# CON_VIDEO_IN.net
KiCad netlist of a schematic drawn in Altium Designer
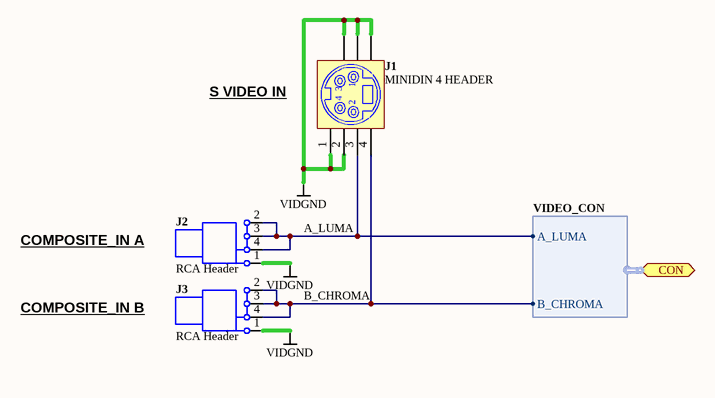
[diagram p0: CON_VIDEO_IN.SchDoc]

(export (version "E")
  (design (tool "Eeschema 10.0.6"))
  (components
    (comp (ref "J1")
      (value "MINIDIN 4 HEADER")
      (footprint "MDJ-F-04")
      (description "Connector, 4850.241, Mini-DIN 4-Way, S-Video/Yellow")
      (libsource (lib "AltiumDesignLibrary") (part "CON-MINIDIN-4-F"))
    )
    (comp (ref "J2")
      (value "RCA Header")
      (footprint "TRC-005")
      (description "Connector, TRC-005-4 , RCA Phono Jack, Right Angle, Thru-Hole, Snap-In")
      (libsource (lib "AltiumDesignLibrary") (part "CON-RCA-RA"))
    )
    (comp (ref "J3")
      (value "RCA Header")
      (footprint "TRC-005")
      (description "Connector, TRC-005-4 , RCA Phono Jack, Right Angle, Thru-Hole, Snap-In")
      (libsource (lib "AltiumDesignLibrary") (part "CON-RCA-RA"))
    )
  )
  (nets
    (net (code "2") (name "/A_LUMA") (class "Default")
      (node (ref "J1") (pin "3") (pinfunction "H_3") (pintype "passive"))
      (node (ref "J2") (pin "2") (pinfunction "Yellow_2") (pintype "passive"))
      (node (ref "J2") (pin "3") (pinfunction "White_3") (pintype "passive"))
      (node (ref "J2") (pin "4") (pinfunction "Red_4") (pintype "passive"))
    )
    (net (code "3") (name "/B_CHROMA") (class "Default")
      (node (ref "J1") (pin "4") (pinfunction "E_4") (pintype "passive"))
      (node (ref "J3") (pin "2") (pinfunction "Yellow_2") (pintype "passive"))
      (node (ref "J3") (pin "3") (pinfunction "White_3") (pintype "passive"))
      (node (ref "J3") (pin "4") (pinfunction "Red_4") (pintype "passive"))
    )
    (net (code "5") (name "VIDGND") (class "Default")
      (node (ref "J1") (pin "1") (pinfunction "D_1") (pintype "passive"))
      (node (ref "J1") (pin "2") (pinfunction "A_2") (pintype "passive"))
      (node (ref "J1") (pin "MH1") (pinfunction "MH1_MH1") (pintype "passive"))
      (node (ref "J1") (pin "MH2") (pinfunction "MH2_MH2") (pintype "passive"))
      (node (ref "J1") (pin "MH3") (pinfunction "MH3_MH3") (pintype "passive"))
      (node (ref "J2") (pin "1") (pinfunction "Black_1") (pintype "passive"))
      (node (ref "J3") (pin "1") (pinfunction "Black_1") (pintype "passive"))
    )
  )
)
